# ir.net
KiCad netlist of a schematic drawn in Altium Designer
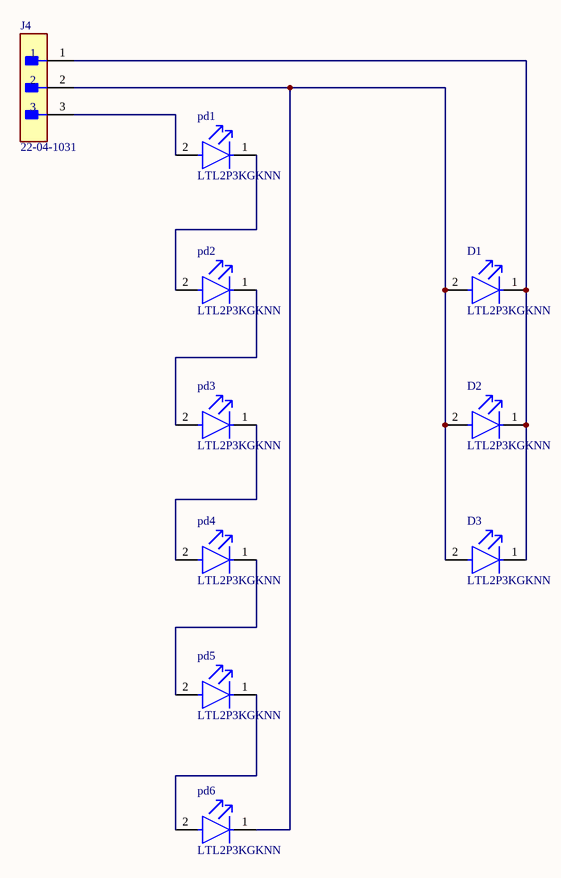
[diagram p0: ir.SchDoc]

(export (version "E")
  (design (tool "Eeschema 10.0.6"))
  (components
    (comp (ref "D1")
      (value "LTL2P3KGKNN")
      (footprint "FP-LTL2P3KGKNN-MFG")
      (description "LED GREEN CLEAR T-1 3/4 T/H")
      (fields
        (field (name "MANUFACTURER") "Lite-On")
        (field (name "OCTOPART") "https://octopart.com/ltl2p3kgknn-lite-on-550036")
      )
      (libsource (lib "Altium Content Vault") (part "8706943c75ba83719d021d2fdc84c58"))
    )
    (comp (ref "D2")
      (value "LTL2P3KGKNN")
      (footprint "FP-LTL2P3KGKNN-MFG")
      (description "LED GREEN CLEAR T-1 3/4 T/H")
      (fields
        (field (name "MANUFACTURER") "Lite-On")
        (field (name "OCTOPART") "https://octopart.com/ltl2p3kgknn-lite-on-550036")
      )
      (libsource (lib "Altium Content Vault") (part "8706943c75ba83719d021d2fdc84c58"))
    )
    (comp (ref "D3")
      (value "LTL2P3KGKNN")
      (footprint "FP-LTL2P3KGKNN-MFG")
      (description "LED GREEN CLEAR T-1 3/4 T/H")
      (fields
        (field (name "MANUFACTURER") "Lite-On")
        (field (name "OCTOPART") "https://octopart.com/ltl2p3kgknn-lite-on-550036")
      )
      (libsource (lib "Altium Content Vault") (part "8706943c75ba83719d021d2fdc84c58"))
    )
    (comp (ref "J4")
      (value "22-04-1031")
      (footprint "FP-22-04-1031-MFG")
      (description "CONN HEADER VERT 3POS 2.5MM")
      (libsource (lib "Altium Content Vault") (part "0d3f023dd272f625e17a2be33dea85f"))
    )
    (comp (ref "pd1")
      (value "LTL2P3KGKNN")
      (footprint "FP-LTL2P3KGKNN-MFG")
      (description "LED GREEN CLEAR T-1 3/4 T/H")
      (fields
        (field (name "MANUFACTURER") "Lite-On")
        (field (name "OCTOPART") "https://octopart.com/ltl2p3kgknn-lite-on-550036")
      )
      (libsource (lib "Altium Content Vault") (part "8706943c75ba83719d021d2fdc84c58"))
    )
    (comp (ref "pd2")
      (value "LTL2P3KGKNN")
      (footprint "FP-LTL2P3KGKNN-MFG")
      (description "LED GREEN CLEAR T-1 3/4 T/H")
      (fields
        (field (name "MANUFACTURER") "Lite-On")
        (field (name "OCTOPART") "https://octopart.com/ltl2p3kgknn-lite-on-550036")
      )
      (libsource (lib "Altium Content Vault") (part "8706943c75ba83719d021d2fdc84c58"))
    )
    (comp (ref "pd3")
      (value "LTL2P3KGKNN")
      (footprint "FP-LTL2P3KGKNN-MFG")
      (description "LED GREEN CLEAR T-1 3/4 T/H")
      (fields
        (field (name "MANUFACTURER") "Lite-On")
        (field (name "OCTOPART") "https://octopart.com/ltl2p3kgknn-lite-on-550036")
      )
      (libsource (lib "Altium Content Vault") (part "8706943c75ba83719d021d2fdc84c58"))
    )
    (comp (ref "pd4")
      (value "LTL2P3KGKNN")
      (footprint "FP-LTL2P3KGKNN-MFG")
      (description "LED GREEN CLEAR T-1 3/4 T/H")
      (fields
        (field (name "MANUFACTURER") "Lite-On")
        (field (name "OCTOPART") "https://octopart.com/ltl2p3kgknn-lite-on-550036")
      )
      (libsource (lib "Altium Content Vault") (part "8706943c75ba83719d021d2fdc84c58"))
    )
    (comp (ref "pd5")
      (value "LTL2P3KGKNN")
      (footprint "FP-LTL2P3KGKNN-MFG")
      (description "LED GREEN CLEAR T-1 3/4 T/H")
      (fields
        (field (name "MANUFACTURER") "Lite-On")
        (field (name "OCTOPART") "https://octopart.com/ltl2p3kgknn-lite-on-550036")
      )
      (libsource (lib "Altium Content Vault") (part "8706943c75ba83719d021d2fdc84c58"))
    )
    (comp (ref "pd6")
      (value "LTL2P3KGKNN")
      (footprint "FP-LTL2P3KGKNN-MFG")
      (description "LED GREEN CLEAR T-1 3/4 T/H")
      (fields
        (field (name "MANUFACTURER") "Lite-On")
        (field (name "OCTOPART") "https://octopart.com/ltl2p3kgknn-lite-on-550036")
      )
      (libsource (lib "Altium Content Vault") (part "8706943c75ba83719d021d2fdc84c58"))
    )
  )
  (nets
    (net (code "1") (name "Net-(D1-A)") (class "Default")
      (node (ref "D1") (pin "2") (pinfunction "A_2") (pintype "passive"))
      (node (ref "D2") (pin "2") (pinfunction "A_2") (pintype "passive"))
      (node (ref "D3") (pin "2") (pinfunction "A_2") (pintype "passive"))
      (node (ref "J4") (pin "2") (pinfunction "2_2") (pintype "passive"))
      (node (ref "pd6") (pin "1") (pinfunction "C_1") (pintype "passive"))
    )
    (net (code "2") (name "Net-(D1-C)") (class "Default")
      (node (ref "D1") (pin "1") (pinfunction "C_1") (pintype "passive"))
      (node (ref "D2") (pin "1") (pinfunction "C_1") (pintype "passive"))
      (node (ref "D3") (pin "1") (pinfunction "C_1") (pintype "passive"))
      (node (ref "J4") (pin "1") (pinfunction "1_1") (pintype "passive"))
    )
    (net (code "3") (name "Net-(pd1-A)") (class "Default")
      (node (ref "J4") (pin "3") (pinfunction "3_3") (pintype "passive"))
      (node (ref "pd1") (pin "2") (pinfunction "A_2") (pintype "passive"))
    )
    (net (code "4") (name "Net-(pd1-C)") (class "Default")
      (node (ref "pd1") (pin "1") (pinfunction "C_1") (pintype "passive"))
      (node (ref "pd2") (pin "2") (pinfunction "A_2") (pintype "passive"))
    )
    (net (code "5") (name "Net-(pd2-C)") (class "Default")
      (node (ref "pd2") (pin "1") (pinfunction "C_1") (pintype "passive"))
      (node (ref "pd3") (pin "2") (pinfunction "A_2") (pintype "passive"))
    )
    (net (code "6") (name "Net-(pd3-C)") (class "Default")
      (node (ref "pd3") (pin "1") (pinfunction "C_1") (pintype "passive"))
      (node (ref "pd4") (pin "2") (pinfunction "A_2") (pintype "passive"))
    )
    (net (code "7") (name "Net-(pd4-C)") (class "Default")
      (node (ref "pd4") (pin "1") (pinfunction "C_1") (pintype "passive"))
      (node (ref "pd5") (pin "2") (pinfunction "A_2") (pintype "passive"))
    )
    (net (code "8") (name "Net-(pd5-C)") (class "Default")
      (node (ref "pd5") (pin "1") (pinfunction "C_1") (pintype "passive"))
      (node (ref "pd6") (pin "2") (pinfunction "A_2") (pintype "passive"))
    )
  )
)
